# switches.net
KiCad netlist of a schematic drawn in Altium Designer
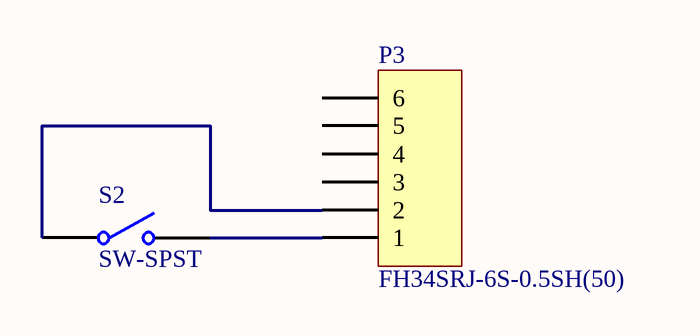
[diagram p0: switches.SchDoc]

(export (version "E")
  (design (tool "Eeschema 10.0.6"))
  (components
    (comp (ref "P3")
      (value "FH34SRJ-6S-0.5SH(50)")
      (footprint "HRS_FH34SRJ-6S-0.5SH(50)")
      (description "Header, 6-Pin")
      (fields (field (name "PUBLISHER") "Altium Limited"))
      (libsource (lib "Miscellaneous Connectors") (part "Header 6"))
    )
    (comp (ref "S2")
      (value "SW-SPST")
      (footprint "ESE22MH24")
      (description "Single-Pole, Single-Throw Switch")
      (fields
        (field (name "MFG") "Panasonic")
        (field (name "MPN") "ESE22MH24")
        (field (name "PUBLISHER") "Altium Limited")
      )
      (libsource (lib "Miscellaneous Devices") (part "SW-SPST"))
    )
  )
  (nets
    (net (code "1") (name "Net-(S2-COMMON)") (class "Default")
      (node (ref "P3") (pin "2") (pinfunction "2_2") (pintype "passive"))
      (node (ref "S2") (pin "1") (pinfunction "COMMON_1") (pintype "passive"))
    )
    (net (code "2") (name "Net-(S2-NO)") (class "Default")
      (node (ref "P3") (pin "1") (pinfunction "1_1") (pintype "passive"))
      (node (ref "S2") (pin "2") (pinfunction "NO_2") (pintype "passive"))
    )
    (net (code "3") (name "unconnected-(P3-Pad3)") (class "Default")
      (node (ref "P3") (pin "3") (pinfunction "3_3") (pintype "passive"))
    )
    (net (code "4") (name "unconnected-(P3-Pad4)") (class "Default")
      (node (ref "P3") (pin "4") (pinfunction "4_4") (pintype "passive"))
    )
    (net (code "5") (name "unconnected-(P3-Pad5)") (class "Default")
      (node (ref "P3") (pin "5") (pinfunction "5_5") (pintype "passive"))
    )
    (net (code "6") (name "unconnected-(P3-Pad6)") (class "Default")
      (node (ref "P3") (pin "6") (pinfunction "6_6") (pintype "passive"))
    )
  )
)
